# core09gnd.net
KiCad netlist of a schematic drawn in EAGLE
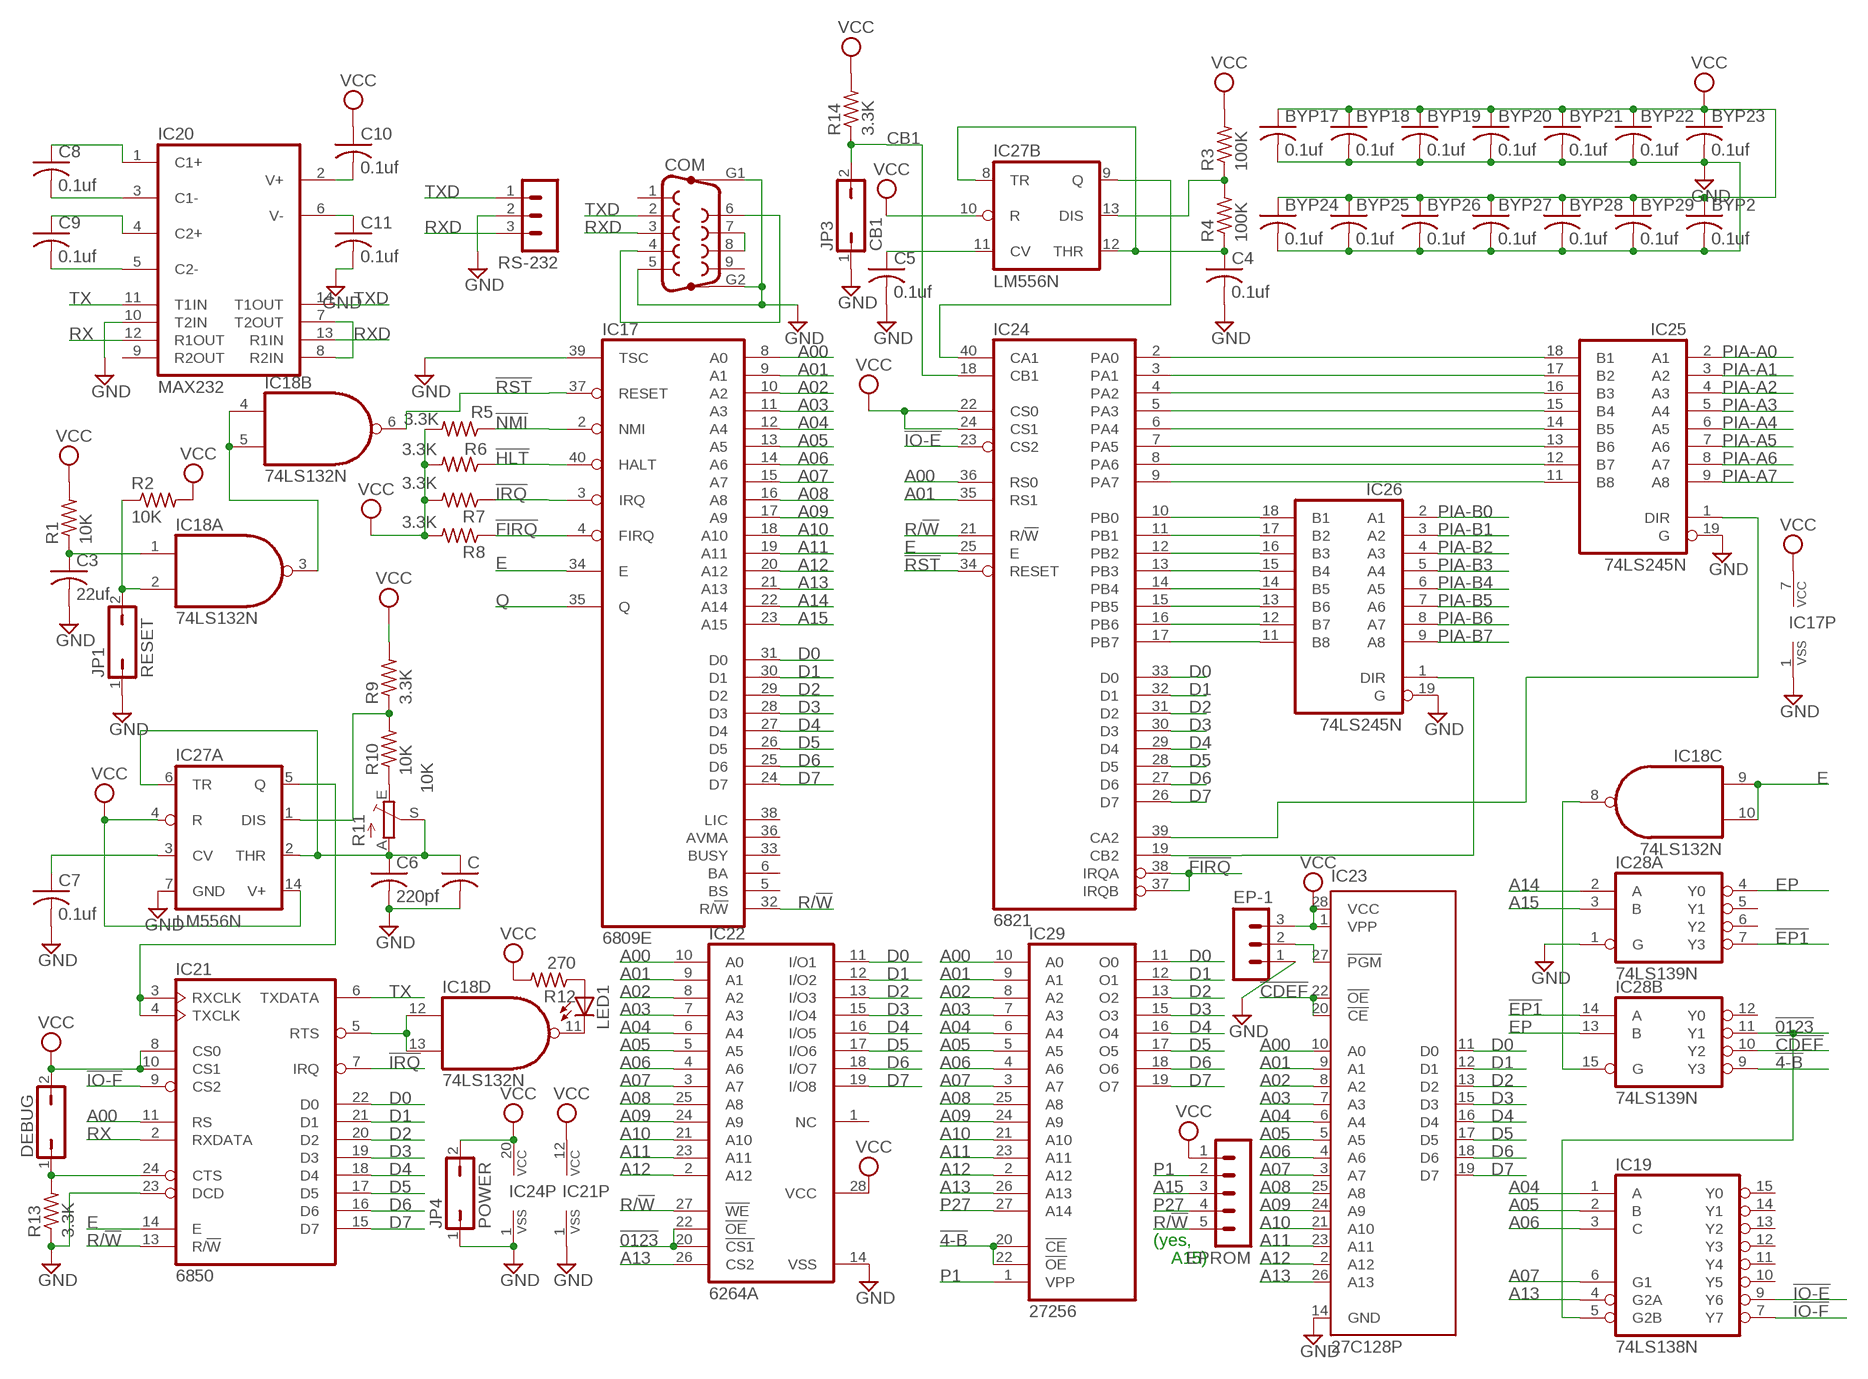
[diagram p0: schematic, sheet 1]
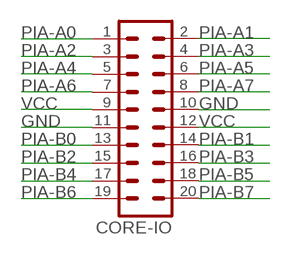
[diagram p1: schematic, sheet 2]
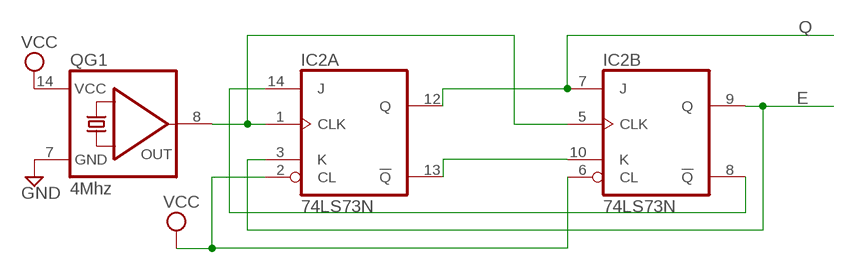
[diagram p2: schematic, sheet 3]

(export (version "E")
  (design (tool "Eeschema 10.0.6"))
  (components
    (comp (ref "CORE-IO")
      (value "MA10-2")
      (footprint "eagle-import:MA10-2")
      (libsource (lib "eagle-import") (part "MA10-2"))
    )
    (comp (ref "IC2")
      (value "74LS73N")
      (footprint "eagle-import:DIL14")
      (libsource (lib "eagle-import") (part "7473NLS"))
    )
    (comp (ref "QG1")
      (value "4Mhz")
      (footprint "eagle-import:DIL14S")
      (libsource (lib "eagle-import") (part "QG5860"))
    )
    (comp (ref "BYP2")
      (value "0.1uf")
      (footprint "eagle-import:C050-025X075")
      (libsource (lib "eagle-import") (part "C-US050-025X075"))
    )
    (comp (ref "BYP17")
      (value "0.1uf")
      (footprint "eagle-import:C050-025X075")
      (libsource (lib "eagle-import") (part "C-US050-025X075"))
    )
    (comp (ref "BYP18")
      (value "0.1uf")
      (footprint "eagle-import:C050-025X075")
      (libsource (lib "eagle-import") (part "C-US050-025X075"))
    )
    (comp (ref "BYP19")
      (value "0.1uf")
      (footprint "eagle-import:C050-025X075")
      (libsource (lib "eagle-import") (part "C-US050-025X075"))
    )
    (comp (ref "BYP20")
      (value "0.1uf")
      (footprint "eagle-import:C050-025X075")
      (libsource (lib "eagle-import") (part "C-US050-025X075"))
    )
    (comp (ref "BYP21")
      (value "0.1uf")
      (footprint "eagle-import:C050-025X075")
      (libsource (lib "eagle-import") (part "C-US050-025X075"))
    )
    (comp (ref "BYP22")
      (value "0.1uf")
      (footprint "eagle-import:C050-025X075")
      (libsource (lib "eagle-import") (part "C-US050-025X075"))
    )
    (comp (ref "BYP23")
      (value "0.1uf")
      (footprint "eagle-import:C050-025X075")
      (libsource (lib "eagle-import") (part "C-US050-025X075"))
    )
    (comp (ref "BYP24")
      (value "0.1uf")
      (footprint "eagle-import:C050-025X075")
      (libsource (lib "eagle-import") (part "C-US050-025X075"))
    )
    (comp (ref "BYP25")
      (value "0.1uf")
      (footprint "eagle-import:C050-025X075")
      (libsource (lib "eagle-import") (part "C-US050-025X075"))
    )
    (comp (ref "BYP26")
      (value "0.1uf")
      (footprint "eagle-import:C050-025X075")
      (libsource (lib "eagle-import") (part "C-US050-025X075"))
    )
    (comp (ref "BYP27")
      (value "0.1uf")
      (footprint "eagle-import:C050-025X075")
      (libsource (lib "eagle-import") (part "C-US050-025X075"))
    )
    (comp (ref "BYP28")
      (value "0.1uf")
      (footprint "eagle-import:C050-025X075")
      (libsource (lib "eagle-import") (part "C-US050-025X075"))
    )
    (comp (ref "BYP29")
      (value "0.1uf")
      (footprint "eagle-import:C050-025X075")
      (libsource (lib "eagle-import") (part "C-US050-025X075"))
    )
    (comp (ref "C")
      (value "C-US050-025X075")
      (footprint "eagle-import:C050-025X075")
      (libsource (lib "eagle-import") (part "C-US050-025X075"))
    )
    (comp (ref "C3")
      (value "22uf")
      (footprint "eagle-import:C102-054X133")
      (libsource (lib "eagle-import") (part "C-US102-054X133"))
    )
    (comp (ref "C4")
      (value "0.1uf")
      (footprint "eagle-import:C050-025X075")
      (libsource (lib "eagle-import") (part "C-US050-025X075"))
    )
    (comp (ref "C5")
      (value "0.1uf")
      (footprint "eagle-import:C050-025X075")
      (libsource (lib "eagle-import") (part "C-US050-025X075"))
    )
    (comp (ref "C6")
      (value "220pf")
      (footprint "eagle-import:C050-025X075")
      (libsource (lib "eagle-import") (part "C-US050-025X075"))
    )
    (comp (ref "C7")
      (value "0.1uf")
      (footprint "eagle-import:C050-025X075")
      (libsource (lib "eagle-import") (part "C-US050-025X075"))
    )
    (comp (ref "C8")
      (value "0.1uf")
      (footprint "eagle-import:C050-025X075")
      (libsource (lib "eagle-import") (part "C-US050-025X075"))
    )
    (comp (ref "C9")
      (value "0.1uf")
      (footprint "eagle-import:C050-025X075")
      (libsource (lib "eagle-import") (part "C-US050-025X075"))
    )
    (comp (ref "C10")
      (value "0.1uf")
      (footprint "eagle-import:C050-025X075")
      (libsource (lib "eagle-import") (part "C-US050-025X075"))
    )
    (comp (ref "C11")
      (value "0.1uf")
      (footprint "eagle-import:C050-025X075")
      (libsource (lib "eagle-import") (part "C-US050-025X075"))
    )
    (comp (ref "COM")
      (value "F09HP")
      (footprint "eagle-import:F09HP")
      (libsource (lib "eagle-import") (part "F09HP"))
    )
    (comp (ref "DEBUG")
      (value "JP1Q")
      (footprint "eagle-import:JP1")
      (libsource (lib "eagle-import") (part "JP1Q"))
    )
    (comp (ref "EP-1")
      (value "MA03-1")
      (footprint "eagle-import:MA03-1")
      (libsource (lib "eagle-import") (part "MA03-1"))
    )
    (comp (ref "EPROM")
      (value "MA05-1")
      (footprint "eagle-import:MA05-1")
      (libsource (lib "eagle-import") (part "MA05-1"))
    )
    (comp (ref "IC17")
      (value "6809E")
      (footprint "eagle-import:DIL40")
      (fields (field (name "MF") "NTE ELECTRONICS") (field (name "MPN") "NTE6809E"))
      (libsource (lib "eagle-import") (part "6809E"))
    )
    (comp (ref "IC18")
      (value "74LS132N")
      (footprint "eagle-import:DIL14")
      (libsource (lib "eagle-import") (part "7400NLS"))
    )
    (comp (ref "IC19")
      (value "74LS138N")
      (footprint "eagle-import:DIL16")
      (libsource (lib "eagle-import") (part "74138NLS"))
    )
    (comp (ref "IC20")
      (value "MAX232")
      (footprint "eagle-import:DIL16")
      (fields (field (name "MF") "MAXIM") (field (name "MPN") "MAX232ACPE+"))
      (libsource (lib "eagle-import") (part "MAX232"))
    )
    (comp (ref "IC21")
      (value "6850")
      (footprint "eagle-import:DIL24")
      (fields (field (name "MF") "NTE ELECTRONICS") (field (name "MPN") "NTE6850"))
      (libsource (lib "eagle-import") (part "6850"))
    )
    (comp (ref "IC22")
      (value "6264A")
      (footprint "eagle-import:DIL28-6")
      (libsource (lib "eagle-import") (part "6264A"))
    )
    (comp (ref "IC23")
      (value "27C128P")
      (footprint "eagle-import:DIL28-6")
      (libsource (lib "eagle-import") (part "27128PC"))
    )
    (comp (ref "IC24")
      (value "6821")
      (footprint "eagle-import:DIL40")
      (fields (field (name "MF") "NTE ELECTRONICS") (field (name "MPN") "NTE6821"))
      (libsource (lib "eagle-import") (part "6821"))
    )
    (comp (ref "IC25")
      (value "74LS245N")
      (footprint "eagle-import:DIL20")
      (libsource (lib "eagle-import") (part "74245NLS"))
    )
    (comp (ref "IC26")
      (value "74LS245N")
      (footprint "eagle-import:DIL20")
      (libsource (lib "eagle-import") (part "74245NLS"))
    )
    (comp (ref "IC27")
      (value "LM556N")
      (footprint "eagle-import:DIL14")
      (libsource (lib "eagle-import") (part "556NLM"))
    )
    (comp (ref "IC28")
      (value "74LS139N")
      (footprint "eagle-import:DIL16")
      (libsource (lib "eagle-import") (part "74139NLS"))
    )
    (comp (ref "IC29")
      (value "27256")
      (footprint "eagle-import:DIL28")
      (libsource (lib "eagle-import") (part "27256"))
    )
    (comp (ref "JP1")
      (value "RESET")
      (footprint "eagle-import:JP1")
      (libsource (lib "eagle-import") (part "JP1Q"))
    )
    (comp (ref "JP3")
      (value "CB1")
      (footprint "eagle-import:JP1")
      (libsource (lib "eagle-import") (part "JP1Q"))
    )
    (comp (ref "JP4")
      (value "POWER")
      (footprint "eagle-import:JP1")
      (libsource (lib "eagle-import") (part "JP1Q"))
    )
    (comp (ref "LED1")
      (value "LED3MM")
      (footprint "eagle-import:LED3MM")
      (libsource (lib "eagle-import") (part "LED3MM"))
    )
    (comp (ref "R1")
      (value "10K")
      (footprint "eagle-import:0207_7")
      (libsource (lib "eagle-import") (part "R-US_0207/7"))
    )
    (comp (ref "R2")
      (value "10K")
      (footprint "eagle-import:0207_7")
      (libsource (lib "eagle-import") (part "R-US_0207/7"))
    )
    (comp (ref "R3")
      (value "100K")
      (footprint "eagle-import:0207_7")
      (libsource (lib "eagle-import") (part "R-US_0207/7"))
    )
    (comp (ref "R4")
      (value "100K")
      (footprint "eagle-import:0207_7")
      (libsource (lib "eagle-import") (part "R-US_0207/7"))
    )
    (comp (ref "R5")
      (value "3.3K")
      (footprint "eagle-import:0207_7")
      (libsource (lib "eagle-import") (part "R-US_0207/7"))
    )
    (comp (ref "R6")
      (value "3.3K")
      (footprint "eagle-import:0207_7")
      (libsource (lib "eagle-import") (part "R-US_0207/7"))
    )
    (comp (ref "R7")
      (value "3.3K")
      (footprint "eagle-import:0207_7")
      (libsource (lib "eagle-import") (part "R-US_0207/7"))
    )
    (comp (ref "R8")
      (value "3.3K")
      (footprint "eagle-import:0207_7")
      (libsource (lib "eagle-import") (part "R-US_0207/7"))
    )
    (comp (ref "R9")
      (value "3.3K")
      (footprint "eagle-import:0207_7")
      (libsource (lib "eagle-import") (part "R-US_0207/7"))
    )
    (comp (ref "R10")
      (value "10K")
      (footprint "eagle-import:0207_7")
      (libsource (lib "eagle-import") (part "R-US_0207/7"))
    )
    (comp (ref "R11")
      (value "10K")
      (footprint "eagle-import:SP19L")
      (libsource (lib "eagle-import") (part "TRIM_EU-B90P"))
    )
    (comp (ref "R12")
      (value "270")
      (footprint "eagle-import:0207_7")
      (libsource (lib "eagle-import") (part "R-US_0207/7"))
    )
    (comp (ref "R13")
      (value "3.3K")
      (footprint "eagle-import:0207_7")
      (libsource (lib "eagle-import") (part "R-US_0207/7"))
    )
    (comp (ref "R14")
      (value "3.3K")
      (footprint "eagle-import:0207_7")
      (libsource (lib "eagle-import") (part "R-US_0207/7"))
    )
    (comp (ref "RS-232")
      (value "MA03-1")
      (footprint "eagle-import:MA03-1")
      (libsource (lib "eagle-import") (part "MA03-1"))
    )
  )
  (nets
    (net (code "1") (name "A00") (class "Default")
      (node (ref "IC17") (pin "8") (pinfunction "A0_8") (pintype "tri_state"))
      (node (ref "IC21") (pin "11") (pinfunction "RS_11") (pintype "input"))
      (node (ref "IC22") (pin "10") (pinfunction "A0_10") (pintype "input"))
      (node (ref "IC23") (pin "10") (pinfunction "A0_10") (pintype "input"))
      (node (ref "IC24") (pin "36") (pinfunction "RS0_36") (pintype "input"))
      (node (ref "IC29") (pin "10") (pinfunction "A0_10") (pintype "input"))
    )
    (net (code "2") (name "A01") (class "Default")
      (node (ref "IC17") (pin "9") (pinfunction "A1_9") (pintype "tri_state"))
      (node (ref "IC22") (pin "9") (pinfunction "A1_9") (pintype "input"))
      (node (ref "IC23") (pin "9") (pinfunction "A1_9") (pintype "input"))
      (node (ref "IC24") (pin "35") (pinfunction "RS1_35") (pintype "input"))
      (node (ref "IC29") (pin "9") (pinfunction "A1_9") (pintype "input"))
    )
    (net (code "3") (name "A02") (class "Default")
      (node (ref "IC17") (pin "10") (pinfunction "A2_10") (pintype "tri_state"))
      (node (ref "IC22") (pin "8") (pinfunction "A2_8") (pintype "input"))
      (node (ref "IC23") (pin "8") (pinfunction "A2_8") (pintype "input"))
      (node (ref "IC29") (pin "8") (pinfunction "A2_8") (pintype "input"))
    )
    (net (code "4") (name "A03") (class "Default")
      (node (ref "IC17") (pin "11") (pinfunction "A3_11") (pintype "tri_state"))
      (node (ref "IC22") (pin "7") (pinfunction "A3_7") (pintype "input"))
      (node (ref "IC23") (pin "7") (pinfunction "A3_7") (pintype "input"))
      (node (ref "IC29") (pin "7") (pinfunction "A3_7") (pintype "input"))
    )
    (net (code "5") (name "A04") (class "Default")
      (node (ref "IC17") (pin "12") (pinfunction "A4_12") (pintype "tri_state"))
      (node (ref "IC19") (pin "1") (pinfunction "A_1") (pintype "input"))
      (node (ref "IC22") (pin "6") (pinfunction "A4_6") (pintype "input"))
      (node (ref "IC23") (pin "6") (pinfunction "A4_6") (pintype "input"))
      (node (ref "IC29") (pin "6") (pinfunction "A4_6") (pintype "input"))
    )
    (net (code "6") (name "A05") (class "Default")
      (node (ref "IC17") (pin "13") (pinfunction "A5_13") (pintype "tri_state"))
      (node (ref "IC19") (pin "2") (pinfunction "B_2") (pintype "input"))
      (node (ref "IC22") (pin "5") (pinfunction "A5_5") (pintype "input"))
      (node (ref "IC23") (pin "5") (pinfunction "A5_5") (pintype "input"))
      (node (ref "IC29") (pin "5") (pinfunction "A5_5") (pintype "input"))
    )
    (net (code "7") (name "A06") (class "Default")
      (node (ref "IC17") (pin "14") (pinfunction "A6_14") (pintype "tri_state"))
      (node (ref "IC19") (pin "3") (pinfunction "C_3") (pintype "input"))
      (node (ref "IC22") (pin "4") (pinfunction "A6_4") (pintype "input"))
      (node (ref "IC23") (pin "4") (pinfunction "A6_4") (pintype "input"))
      (node (ref "IC29") (pin "4") (pinfunction "A6_4") (pintype "input"))
    )
    (net (code "8") (name "A07") (class "Default")
      (node (ref "IC17") (pin "15") (pinfunction "A7_15") (pintype "tri_state"))
      (node (ref "IC19") (pin "6") (pinfunction "G1_6") (pintype "input"))
      (node (ref "IC22") (pin "3") (pinfunction "A7_3") (pintype "input"))
      (node (ref "IC23") (pin "3") (pinfunction "A7_3") (pintype "input"))
      (node (ref "IC29") (pin "3") (pinfunction "A7_3") (pintype "input"))
    )
    (net (code "9") (name "A08") (class "Default")
      (node (ref "IC17") (pin "16") (pinfunction "A8_16") (pintype "tri_state"))
      (node (ref "IC22") (pin "25") (pinfunction "A8_25") (pintype "input"))
      (node (ref "IC23") (pin "25") (pinfunction "A8_25") (pintype "input"))
      (node (ref "IC29") (pin "25") (pinfunction "A8_25") (pintype "input"))
    )
    (net (code "10") (name "A09") (class "Default")
      (node (ref "IC17") (pin "17") (pinfunction "A9_17") (pintype "tri_state"))
      (node (ref "IC22") (pin "24") (pinfunction "A9_24") (pintype "input"))
      (node (ref "IC23") (pin "24") (pinfunction "A9_24") (pintype "input"))
      (node (ref "IC29") (pin "24") (pinfunction "A9_24") (pintype "input"))
    )
    (net (code "11") (name "A10") (class "Default")
      (node (ref "IC17") (pin "18") (pinfunction "A10_18") (pintype "tri_state"))
      (node (ref "IC22") (pin "21") (pinfunction "A10_21") (pintype "input"))
      (node (ref "IC23") (pin "21") (pinfunction "A10_21") (pintype "input"))
      (node (ref "IC29") (pin "21") (pinfunction "A10_21") (pintype "input"))
    )
    (net (code "12") (name "A11") (class "Default")
      (node (ref "IC17") (pin "19") (pinfunction "A11_19") (pintype "tri_state"))
      (node (ref "IC22") (pin "23") (pinfunction "A11_23") (pintype "input"))
      (node (ref "IC23") (pin "23") (pinfunction "A11_23") (pintype "input"))
      (node (ref "IC29") (pin "23") (pinfunction "A11_23") (pintype "input"))
    )
    (net (code "13") (name "A12") (class "Default")
      (node (ref "IC17") (pin "20") (pinfunction "A12_20") (pintype "tri_state"))
      (node (ref "IC22") (pin "2") (pinfunction "A12_2") (pintype "input"))
      (node (ref "IC23") (pin "2") (pinfunction "A12_2") (pintype "input"))
      (node (ref "IC29") (pin "2") (pinfunction "A12_2") (pintype "input"))
    )
    (net (code "14") (name "A13") (class "Default")
      (node (ref "IC17") (pin "21") (pinfunction "A13_21") (pintype "tri_state"))
      (node (ref "IC19") (pin "4") (pinfunction "G2A_4") (pintype "input"))
      (node (ref "IC22") (pin "26") (pinfunction "CS2_26") (pintype "input"))
      (node (ref "IC23") (pin "26") (pinfunction "A13_26") (pintype "input"))
      (node (ref "IC29") (pin "26") (pinfunction "A13_26") (pintype "input"))
    )
    (net (code "15") (name "A14") (class "Default")
      (node (ref "IC17") (pin "22") (pinfunction "A14_22") (pintype "tri_state"))
      (node (ref "IC28") (pin "2") (pinfunction "A_2") (pintype "input"))
    )
    (net (code "16") (name "A15") (class "Default")
      (node (ref "EPROM") (pin "3") (pinfunction "3_3") (pintype "passive"))
      (node (ref "IC17") (pin "23") (pinfunction "A15_23") (pintype "tri_state"))
      (node (ref "IC28") (pin "3") (pinfunction "B_3") (pintype "input"))
    )
    (net (code "17") (name "CB1") (class "Default")
      (node (ref "IC24") (pin "18") (pinfunction "CB1_18") (pintype "input"))
      (node (ref "JP3") (pin "2") (pinfunction "2_2") (pintype "passive"))
      (node (ref "R14") (pin "1") (pinfunction "1_1") (pintype "passive"))
    )
    (net (code "18") (name "D0") (class "Default")
      (node (ref "IC17") (pin "31") (pinfunction "D0_31") (pintype "bidirectional"))
      (node (ref "IC21") (pin "22") (pinfunction "D0_22") (pintype "bidirectional"))
      (node (ref "IC22") (pin "11") (pinfunction "I/O1_11") (pintype "bidirectional"))
      (node (ref "IC23") (pin "11") (pinfunction "D0_11") (pintype "tri_state"))
      (node (ref "IC24") (pin "33") (pinfunction "D0_33") (pintype "bidirectional"))
      (node (ref "IC29") (pin "11") (pinfunction "O0_11") (pintype "tri_state"))
    )
    (net (code "19") (name "D1") (class "Default")
      (node (ref "IC17") (pin "30") (pinfunction "D1_30") (pintype "bidirectional"))
      (node (ref "IC21") (pin "21") (pinfunction "D1_21") (pintype "bidirectional"))
      (node (ref "IC22") (pin "12") (pinfunction "I/O2_12") (pintype "bidirectional"))
      (node (ref "IC23") (pin "12") (pinfunction "D1_12") (pintype "tri_state"))
      (node (ref "IC24") (pin "32") (pinfunction "D1_32") (pintype "bidirectional"))
      (node (ref "IC29") (pin "12") (pinfunction "O1_12") (pintype "tri_state"))
    )
    (net (code "20") (name "D2") (class "Default")
      (node (ref "IC17") (pin "29") (pinfunction "D2_29") (pintype "bidirectional"))
      (node (ref "IC21") (pin "20") (pinfunction "D2_20") (pintype "bidirectional"))
      (node (ref "IC22") (pin "13") (pinfunction "I/O3_13") (pintype "bidirectional"))
      (node (ref "IC23") (pin "13") (pinfunction "D2_13") (pintype "tri_state"))
      (node (ref "IC24") (pin "31") (pinfunction "D2_31") (pintype "bidirectional"))
      (node (ref "IC29") (pin "13") (pinfunction "O2_13") (pintype "tri_state"))
    )
    (net (code "21") (name "D3") (class "Default")
      (node (ref "IC17") (pin "28") (pinfunction "D3_28") (pintype "bidirectional"))
      (node (ref "IC21") (pin "19") (pinfunction "D3_19") (pintype "bidirectional"))
      (node (ref "IC22") (pin "15") (pinfunction "I/O4_15") (pintype "bidirectional"))
      (node (ref "IC23") (pin "15") (pinfunction "D3_15") (pintype "tri_state"))
      (node (ref "IC24") (pin "30") (pinfunction "D3_30") (pintype "bidirectional"))
      (node (ref "IC29") (pin "15") (pinfunction "O3_15") (pintype "tri_state"))
    )
    (net (code "22") (name "D4") (class "Default")
      (node (ref "IC17") (pin "27") (pinfunction "D4_27") (pintype "bidirectional"))
      (node (ref "IC21") (pin "18") (pinfunction "D4_18") (pintype "bidirectional"))
      (node (ref "IC22") (pin "16") (pinfunction "I/O5_16") (pintype "bidirectional"))
      (node (ref "IC23") (pin "16") (pinfunction "D4_16") (pintype "tri_state"))
      (node (ref "IC24") (pin "29") (pinfunction "D4_29") (pintype "bidirectional"))
      (node (ref "IC29") (pin "16") (pinfunction "O4_16") (pintype "tri_state"))
    )
    (net (code "23") (name "D5") (class "Default")
      (node (ref "IC17") (pin "26") (pinfunction "D5_26") (pintype "bidirectional"))
      (node (ref "IC21") (pin "17") (pinfunction "D5_17") (pintype "bidirectional"))
      (node (ref "IC22") (pin "17") (pinfunction "I/O6_17") (pintype "bidirectional"))
      (node (ref "IC23") (pin "17") (pinfunction "D5_17") (pintype "tri_state"))
      (node (ref "IC24") (pin "28") (pinfunction "D5_28") (pintype "bidirectional"))
      (node (ref "IC29") (pin "17") (pinfunction "O5_17") (pintype "tri_state"))
    )
    (net (code "24") (name "D6") (class "Default")
      (node (ref "IC17") (pin "25") (pinfunction "D6_25") (pintype "bidirectional"))
      (node (ref "IC21") (pin "16") (pinfunction "D6_16") (pintype "bidirectional"))
      (node (ref "IC22") (pin "18") (pinfunction "I/O7_18") (pintype "bidirectional"))
      (node (ref "IC23") (pin "18") (pinfunction "D6_18") (pintype "tri_state"))
      (node (ref "IC24") (pin "27") (pinfunction "D6_27") (pintype "bidirectional"))
      (node (ref "IC29") (pin "18") (pinfunction "O6_18") (pintype "tri_state"))
    )
    (net (code "25") (name "D7") (class "Default")
      (node (ref "IC17") (pin "24") (pinfunction "D7_24") (pintype "bidirectional"))
      (node (ref "IC21") (pin "15") (pinfunction "D7_15") (pintype "bidirectional"))
      (node (ref "IC22") (pin "19") (pinfunction "I/O8_19") (pintype "bidirectional"))
      (node (ref "IC23") (pin "19") (pinfunction "D7_19") (pintype "tri_state"))
      (node (ref "IC24") (pin "26") (pinfunction "D7_26") (pintype "bidirectional"))
      (node (ref "IC29") (pin "19") (pinfunction "O7_19") (pintype "tri_state"))
    )
    (net (code "26") (name "E") (class "Default")
      (node (ref "IC17") (pin "34") (pinfunction "E_34") (pintype "input"))
      (node (ref "IC18") (pin "10") (pinfunction "I1_10") (pintype "input"))
      (node (ref "IC18") (pin "9") (pinfunction "I0_9") (pintype "input"))
      (node (ref "IC2") (pin "3") (pinfunction "K_3") (pintype "input"))
      (node (ref "IC2") (pin "9") (pinfunction "Q_9") (pintype "output"))
      (node (ref "IC21") (pin "14") (pinfunction "E_14") (pintype "input"))
      (node (ref "IC24") (pin "25") (pinfunction "E_25") (pintype "input"))
    )
    (net (code "27") (name "EP") (class "Default")
      (node (ref "IC28") (pin "13") (pinfunction "B_13") (pintype "input"))
      (node (ref "IC28") (pin "4") (pinfunction "Y0_4") (pintype "output"))
    )
    (net (code "28") (name "GND") (class "Default")
      (node (ref "BYP17") (pin "2") (pinfunction "2_2") (pintype "passive"))
      (node (ref "BYP18") (pin "2") (pinfunction "2_2") (pintype "passive"))
      (node (ref "BYP19") (pin "2") (pinfunction "2_2") (pintype "passive"))
      (node (ref "BYP2") (pin "2") (pinfunction "2_2") (pintype "passive"))
      (node (ref "BYP20") (pin "2") (pinfunction "2_2") (pintype "passive"))
      (node (ref "BYP21") (pin "2") (pinfunction "2_2") (pintype "passive"))
      (node (ref "BYP22") (pin "2") (pinfunction "2_2") (pintype "passive"))
      (node (ref "BYP23") (pin "2") (pinfunction "2_2") (pintype "passive"))
      (node (ref "BYP24") (pin "2") (pinfunction "2_2") (pintype "passive"))
      (node (ref "BYP25") (pin "2") (pinfunction "2_2") (pintype "passive"))
      (node (ref "BYP26") (pin "2") (pinfunction "2_2") (pintype "passive"))
      (node (ref "BYP27") (pin "2") (pinfunction "2_2") (pintype "passive"))
      (node (ref "BYP28") (pin "2") (pinfunction "2_2") (pintype "passive"))
      (node (ref "BYP29") (pin "2") (pinfunction "2_2") (pintype "passive"))
      (node (ref "C") (pin "2") (pinfunction "2_2") (pintype "passive"))
      (node (ref "C11") (pin "2") (pinfunction "2_2") (pintype "passive"))
      (node (ref "C3") (pin "2") (pinfunction "2_2") (pintype "passive"))
      (node (ref "C4") (pin "2") (pinfunction "2_2") (pintype "passive"))
      (node (ref "C5") (pin "2") (pinfunction "2_2") (pintype "passive"))
      (node (ref "C6") (pin "2") (pinfunction "2_2") (pintype "passive"))
      (node (ref "C7") (pin "2") (pinfunction "2_2") (pintype "passive"))
      (node (ref "COM") (pin "5") (pinfunction "5_5") (pintype "passive"))
      (node (ref "COM") (pin "G1") (pinfunction "G1_G1") (pintype "passive"))
      (node (ref "COM") (pin "G2") (pinfunction "G2_G2") (pintype "passive"))
      (node (ref "CORE-IO") (pin "10") (pinfunction "10_10") (pintype "passive"))
      (node (ref "CORE-IO") (pin "11") (pinfunction "11_11") (pintype "passive"))
      (node (ref "EP-1") (pin "1") (pinfunction "1_1") (pintype "passive"))
      (node (ref "IC17") (pin "1") (pinfunction "VSS_1") (pintype "power_in"))
      (node (ref "IC17") (pin "39") (pinfunction "TSC_39") (pintype "input"))
      (node (ref "IC20") (pin "10") (pinfunction "T2IN_10") (pintype "input"))
      (node (ref "IC21") (pin "1") (pinfunction "VSS_1") (pintype "power_in"))
      (node (ref "IC21") (pin "23") (pinfunction "DCD_23") (pintype "input"))
      (node (ref "IC22") (pin "14") (pinfunction "VSS_14") (pintype "power_in"))
      (node (ref "IC23") (pin "14") (pinfunction "GND_14") (pintype "power_in"))
      (node (ref "IC24") (pin "1") (pinfunction "VSS_1") (pintype "power_in"))
      (node (ref "IC25") (pin "19") (pinfunction "G_19") (pintype "input"))
      (node (ref "IC26") (pin "19") (pinfunction "G_19") (pintype "input"))
      (node (ref "IC27") (pin "7") (pinfunction "GND_7") (pintype "power_in"))
      (node (ref "IC28") (pin "1") (pinfunction "G_1") (pintype "input"))
      (node (ref "JP1") (pin "1") (pinfunction "1_1") (pintype "passive"))
      (node (ref "JP3") (pin "1") (pinfunction "1_1") (pintype "passive"))
      (node (ref "JP4") (pin "1") (pinfunction "1_1") (pintype "passive"))
      (node (ref "QG1") (pin "7") (pinfunction "GND_7") (pintype "power_in"))
      (node (ref "R13") (pin "1") (pinfunction "1_1") (pintype "passive"))
      (node (ref "RS-232") (pin "2") (pinfunction "2_2") (pintype "passive"))
    )
    (net (code "29") (name "Net-(COM-Pad4)") (class "Default")
      (node (ref "COM") (pin "4") (pinfunction "4_4") (pintype "passive"))
      (node (ref "COM") (pin "6") (pinfunction "6_6") (pintype "passive"))
    )
    (net (code "30") (name "Net-(COM-Pad7)") (class "Default")
      (node (ref "COM") (pin "7") (pinfunction "7_7") (pintype "passive"))
      (node (ref "COM") (pin "8") (pinfunction "8_8") (pintype "passive"))
    )
    (net (code "31") (name "Net-(IC2A-CLK)") (class "Default")
      (node (ref "IC2") (pin "1") (pinfunction "CLK_1") (pintype "input"))
      (node (ref "IC2") (pin "5") (pinfunction "CLK_5") (pintype "input"))
      (node (ref "QG1") (pin "8") (pinfunction "OUT_8") (pintype "output"))
    )
    (net (code "32") (name "Net-(IC2A-J)") (class "Default")
      (node (ref "IC2") (pin "14") (pinfunction "J_14") (pintype "input"))
      (node (ref "IC2") (pin "8") (pinfunction "~{Q}_8") (pintype "output"))
    )
    (net (code "33") (name "Net-(IC2A-~{Q})") (class "Default")
      (node (ref "IC2") (pin "10") (pinfunction "K_10") (pintype "input"))
      (node (ref "IC2") (pin "13") (pinfunction "~{Q}_13") (pintype "output"))
    )
    (net (code "34") (name "Net-(IC18A-I0)") (class "Default")
      (node (ref "C3") (pin "1") (pinfunction "1_1") (pintype "passive"))
      (node (ref "IC18") (pin "1") (pinfunction "I0_1") (pintype "input"))
      (node (ref "R1") (pin "1") (pinfunction "1_1") (pintype "passive"))
    )
    (net (code "35") (name "Net-(IC18A-I1)") (class "Default")
      (node (ref "IC18") (pin "2") (pinfunction "I1_2") (pintype "input"))
      (node (ref "JP1") (pin "2") (pinfunction "2_2") (pintype "passive"))
      (node (ref "R2") (pin "1") (pinfunction "1_1") (pintype "passive"))
    )
    (net (code "36") (name "Net-(IC18A-O)") (class "Default")
      (node (ref "IC18") (pin "3") (pinfunction "O_3") (pintype "output"))
      (node (ref "IC18") (pin "4") (pinfunction "I0_4") (pintype "input"))
      (node (ref "IC18") (pin "5") (pinfunction "I1_5") (pintype "input"))
    )
    (net (code "37") (name "Net-(IC18C-O)") (class "Default")
      (node (ref "IC18") (pin "8") (pinfunction "O_8") (pintype "output"))
      (node (ref "IC28") (pin "15") (pinfunction "G_15") (pintype "input"))
    )
    (net (code "38") (name "Net-(IC18D-I0)") (class "Default")
      (node (ref "IC18") (pin "12") (pinfunction "I0_12") (pintype "input"))
      (node (ref "IC18") (pin "13") (pinfunction "I1_13") (pintype "input"))
      (node (ref "IC21") (pin "5") (pinfunction "RTS_5") (pintype "output"))
    )
    (net (code "39") (name "Net-(IC18D-O)") (class "Default")
      (node (ref "IC18") (pin "11") (pinfunction "O_11") (pintype "output"))
      (node (ref "LED1") (pin "K") (pinfunction "C_K") (pintype "passive"))
    )
    (net (code "40") (name "Net-(IC20A-C1+)") (class "Default")
      (node (ref "C8") (pin "1") (pinfunction "1_1") (pintype "passive"))
      (node (ref "IC20") (pin "1") (pinfunction "C1+_1") (pintype "bidirectional"))
    )
    (net (code "41") (name "Net-(IC20A-C1-)") (class "Default")
      (node (ref "C8") (pin "2") (pinfunction "2_2") (pintype "passive"))
      (node (ref "IC20") (pin "3") (pinfunction "C1-_3") (pintype "bidirectional"))
    )
    (net (code "42") (name "Net-(IC20A-C2+)") (class "Default")
      (node (ref "C9") (pin "1") (pinfunction "1_1") (pintype "passive"))
      (node (ref "IC20") (pin "4") (pinfunction "C2+_4") (pintype "bidirectional"))
    )
    (net (code "43") (name "Net-(IC20A-C2-)") (class "Default")
      (node (ref "C9") (pin "2") (pinfunction "2_2") (pintype "passive"))
      (node (ref "IC20") (pin "5") (pinfunction "C2-_5") (pintype "bidirectional"))
    )
    (net (code "44") (name "Net-(IC20A-R2IN)") (class "Default")
      (node (ref "IC20") (pin "7") (pinfunction "T2OUT_7") (pintype "output"))
      (node (ref "IC20") (pin "8") (pinfunction "R2IN_8") (pintype "input"))
    )
    (net (code "45") (name "Net-(IC20A-V+)") (class "Default")
      (node (ref "C10") (pin "2") (pinfunction "2_2") (pintype "passive"))
      (node (ref "IC20") (pin "2") (pinfunction "V+_2") (pintype "bidirectional"))
    )
    (net (code "46") (name "Net-(IC20A-V-)") (class "Default")
      (node (ref "C11") (pin "1") (pinfunction "1_1") (pintype "passive"))
      (node (ref "IC20") (pin "6") (pinfunction "V-_6") (pintype "bidirectional"))
    )
    (net (code "47") (name "Net-(IC21A-CTS)") (class "Default")
      (node (ref "DEBUG") (pin "1") (pinfunction "1_1") (pintype "passive"))
      (node (ref "IC21") (pin "24") (pinfunction "CTS_24") (pintype "input"))
      (node (ref "R13") (pin "2") (pinfunction "2_2") (pintype "passive"))
    )
    (net (code "48") (name "Net-(IC21A-RXCLK)") (class "Default")
      (node (ref "IC21") (pin "3") (pinfunction "RXCLK_3") (pintype "input"))
      (node (ref "IC21") (pin "4") (pinfunction "TXCLK_4") (pintype "input"))
      (node (ref "IC27") (pin "5") (pinfunction "Q_5") (pintype "output"))
    )
    (net (code "49") (name "Net-(IC23-~{PGM})") (class "Default")
      (node (ref "EP-1") (pin "2") (pinfunction "2_2") (pintype "passive"))
      (node (ref "IC23") (pin "27") (pinfunction "~{PGM}_27") (pintype "passive"))
    )
    (net (code "50") (name "Net-(IC24A-CA1)") (class "Default")
      (node (ref "IC24") (pin "40") (pinfunction "CA1_40") (pintype "input"))
      (node (ref "IC27") (pin "9") (pinfunction "Q_9") (pintype "output"))
    )
    (net (code "51") (name "Net-(IC24A-CA2)") (class "Default")
      (node (ref "IC24") (pin "39") (pinfunction "CA2_39") (pintype "bidirectional"))
      (node (ref "IC25") (pin "1") (pinfunction "DIR_1") (pintype "input"))
    )
    (net (code "52") (name "Net-(IC24A-CB2)") (class "Default")
      (node (ref "IC24") (pin "19") (pinfunction "CB2_19") (pintype "bidirectional"))
      (node (ref "IC26") (pin "1") (pinfunction "DIR_1") (pintype "input"))
    )
    (net (code "53") (name "Net-(IC24A-PA0)") (class "Default")
      (node (ref "IC24") (pin "2") (pinfunction "PA0_2") (pintype "bidirectional"))
      (node (ref "IC25") (pin "18") (pinfunction "B1_18") (pintype "bidirectional"))
    )
    (net (code "54") (name "Net-(IC24A-PA1)") (class "Default")
      (node (ref "IC24") (pin "3") (pinfunction "PA1_3") (pintype "bidirectional"))
      (node (ref "IC25") (pin "17") (pinfunction "B2_17") (pintype "bidirectional"))
    )
    (net (code "55") (name "Net-(IC24A-PA2)") (class "Default")
      (node (ref "IC24") (pin "4") (pinfunction "PA2_4") (pintype "bidirectional"))
      (node (ref "IC25") (pin "16") (pinfunction "B3_16") (pintype "bidirectional"))
    )
    (net (code "56") (name "Net-(IC24A-PA3)") (class "Default")
      (node (ref "IC24") (pin "5") (pinfunction "PA3_5") (pintype "bidirectional"))
      (node (ref "IC25") (pin "15") (pinfunction "B4_15") (pintype "bidirectional"))
    )
    (net (code "57") (name "Net-(IC24A-PA4)") (class "Default")
      (node (ref "IC24") (pin "6") (pinfunction "PA4_6") (pintype "bidirectional"))
      (node (ref "IC25") (pin "14") (pinfunction "B5_14") (pintype "bidirectional"))
    )
    (net (code "58") (name "Net-(IC24A-PA5)") (class "Default")
      (node (ref "IC24") (pin "7") (pinfunction "PA5_7") (pintype "bidirectional"))
      (node (ref "IC25") (pin "13") (pinfunction "B6_13") (pintype "bidirectional"))
    )
    (net (code "59") (name "Net-(IC24A-PA6)") (class "Default")
      (node (ref "IC24") (pin "8") (pinfunction "PA6_8") (pintype "bidirectional"))
      (node (ref "IC25") (pin "12") (pinfunction "B7_12") (pintype "bidirectional"))
    )
    (net (code "60") (name "Net-(IC24A-PA7)") (class "Default")
      (node (ref "IC24") (pin "9") (pinfunction "PA7_9") (pintype "bidirectional"))
      (node (ref "IC25") (pin "11") (pinfunction "B8_11") (pintype "bidirectional"))
    )
    (net (code "61") (name "Net-(IC24A-PB0)") (class "Default")
      (node (ref "IC24") (pin "10") (pinfunction "PB0_10") (pintype "bidirectional"))
      (node (ref "IC26") (pin "18") (pinfunction "B1_18") (pintype "bidirectional"))
    )
    (net (code "62") (name "Net-(IC24A-PB1)") (class "Default")
      (node (ref "IC24") (pin "11") (pinfunction "PB1_11") (pintype "bidirectional"))
      (node (ref "IC26") (pin "17") (pinfunction "B2_17") (pintype "bidirectional"))
    )
    (net (code "63") (name "Net-(IC24A-PB2)") (class "Default")
      (node (ref "IC24") (pin "12") (pinfunction "PB2_12") (pintype "bidirectional"))
      (node (ref "IC26") (pin "16") (pinfunction "B3_16") (pintype "bidirectional"))
    )
    (net (code "64") (name "Net-(IC24A-PB3)") (class "Default")
      (node (ref "IC24") (pin "13") (pinfunction "PB3_13") (pintype "bidirectional"))
      (node (ref "IC26") (pin "15") (pinfunction "B4_15") (pintype "bidirectional"))
    )
    (net (code "65") (name "Net-(IC24A-PB4)") (class "Default")
      (node (ref "IC24") (pin "14") (pinfunction "PB4_14") (pintype "bidirectional"))
      (node (ref "IC26") (pin "14") (pinfunction "B5_14") (pintype "bidirectional"))
    )
    (net (code "66") (name "Net-(IC24A-PB5)") (class "Default")
      (node (ref "IC24") (pin "15") (pinfunction "PB5_15") (pintype "bidirectional"))
      (node (ref "IC26") (pin "13") (pinfunction "B6_13") (pintype "bidirectional"))
    )
    (net (code "67") (name "Net-(IC24A-PB6)") (class "Default")
      (node (ref "IC24") (pin "16") (pinfunction "PB6_16") (pintype "bidirectional"))
      (node (ref "IC26") (pin "12") (pinfunction "B7_12") (pintype "bidirectional"))
    )
    (net (code "68") (name "Net-(IC24A-PB7)") (class "Default")
      (node (ref "IC24") (pin "17") (pinfunction "PB7_17") (pintype "bidirectional"))
      (node (ref "IC26") (pin "11") (pinfunction "B8_11") (pintype "bidirectional"))
    )
    (net (code "69") (name "Net-(IC27A-CV)") (class "Default")
      (node (ref "C7") (pin "1") (pinfunction "1_1") (pintype "passive"))
      (node (ref "IC27") (pin "3") (pinfunction "CV_3") (pintype "input"))
    )
    (net (code "70") (name "Net-(IC27A-DIS)") (class "Default")
      (node (ref "IC27") (pin "1") (pinfunction "DIS_1") (pintype "input"))
      (node (ref "R10") (pin "2") (pinfunction "2_2") (pintype "passive"))
      (node (ref "R9") (pin "1") (pinfunction "1_1") (pintype "passive"))
    )
    (net (code "71") (name "Net-(IC27A-THR)") (class "Default")
      (node (ref "C") (pin "1") (pinfunction "1_1") (pintype "passive"))
      (node (ref "C6") (pin "1") (pinfunction "1_1") (pintype "passive"))
      (node (ref "IC27") (pin "2") (pinfunction "THR_2") (pintype "input"))
      (node (ref "IC27") (pin "6") (pinfunction "TR_6") (pintype "input"))
      (node (ref "R11") (pin "A") (pinfunction "A_A") (pintype "passive"))
      (node (ref "R11") (pin "S") (pinfunction "S_S") (pintype "passive"))
    )
    (net (code "72") (name "Net-(IC27B-CV)") (class "Default")
      (node (ref "C5") (pin "1") (pinfunction "1_1") (pintype "passive"))
      (node (ref "IC27") (pin "11") (pinfunction "CV_11") (pintype "input"))
    )
    (net (code "73") (name "Net-(IC27B-DIS)") (class "Default")
      (node (ref "IC27") (pin "13") (pinfunction "DIS_13") (pintype "input"))
      (node (ref "R3") (pin "1") (pinfunction "1_1") (pintype "passive"))
      (node (ref "R4") (pin "2") (pinfunction "2_2") (pintype "passive"))
    )
    (net (code "74") (name "Net-(IC27B-THR)") (class "Default")
      (node (ref "C4") (pin "1") (pinfunction "1_1") (pintype "passive"))
      (node (ref "IC27") (pin "12") (pinfunction "THR_12") (pintype "input"))
      (node (ref "IC27") (pin "8") (pinfunction "TR_8") (pintype "input"))
      (node (ref "R4") (pin "1") (pinfunction "1_1") (pintype "passive"))
    )
    (net (code "75") (name "Net-(LED1-PadA)") (class "Default")
      (node (ref "LED1") (pin "A") (pinfunction "A_A") (pintype "passive"))
      (node (ref "R12") (pin "1") (pinfunction "1_1") (pintype "passive"))
    )
    (net (code "76") (name "Net-(R10-Pad1)") (class "Default")
      (node (ref "R10") (pin "1") (pinfunction "1_1") (pintype "passive"))
      (node (ref "R11") (pin "E") (pinfunction "E_E") (pintype "passive"))
    )
    (net (code "77") (name "P1") (class "Default")
      (node (ref "EPROM") (pin "2") (pinfunction "2_2") (pintype "passive"))
      (node (ref "IC29") (pin "1") (pinfunction "VPP_1") (pintype "input"))
    )
    (net (code "78") (name "P27") (class "Default")
      (node (ref "EPROM") (pin "4") (pinfunction "4_4") (pintype "passive"))
      (node (ref "IC29") (pin "27") (pinfunction "A14_27") (pintype "input"))
    )
    (net (code "79") (name "PIA-A0") (class "Default")
      (node (ref "CORE-IO") (pin "1") (pinfunction "1_1") (pintype "passive"))
      (node (ref "IC25") (pin "2") (pinfunction "A1_2") (pintype "bidirectional"))
    )
    (net (code "80") (name "PIA-A1") (class "Default")
      (node (ref "CORE-IO") (pin "2") (pinfunction "2_2") (pintype "passive"))
      (node (ref "IC25") (pin "3") (pinfunction "A2_3") (pintype "bidirectional"))
    )
    (net (code "81") (name "PIA-A2") (class "Default")
      (node (ref "CORE-IO") (pin "3") (pinfunction "3_3") (pintype "passive"))
      (node (ref "IC25") (pin "4") (pinfunction "A3_4") (pintype "bidirectional"))
    )
    (net (code "82") (name "PIA-A3") (class "Default")
      (node (ref "CORE-IO") (pin "4") (pinfunction "4_4") (pintype "passive"))
      (node (ref "IC25") (pin "5") (pinfunction "A4_5") (pintype "bidirectional"))
    )
    (net (code "83") (name "PIA-A4") (class "Default")
      (node (ref "CORE-IO") (pin "5") (pinfunction "5_5") (pintype "passive"))
      (node (ref "IC25") (pin "6") (pinfunction "A5_6") (pintype "bidirectional"))
    )
    (net (code "84") (name "PIA-A5") (class "Default")
      (node (ref "CORE-IO") (pin "6") (pinfunction "6_6") (pintype "passive"))
      (node (ref "IC25") (pin "7") (pinfunction "A6_7") (pintype "bidirectional"))
    )
    (net (code "85") (name "PIA-A6") (class "Default")
      (node (ref "CORE-IO") (pin "7") (pinfunction "7_7") (pintype "passive"))
      (node (ref "IC25") (pin "8") (pinfunction "A7_8") (pintype "bidirectional"))
    )
    (net (code "86") (name "PIA-A7") (class "Default")
      (node (ref "CORE-IO") (pin "8") (pinfunction "8_8") (pintype "passive"))
      (node (ref "IC25") (pin "9") (pinfunction "A8_9") (pintype "bidirectional"))
    )
    (net (code "87") (name "PIA-B0") (class "Default")
      (node (ref "CORE-IO") (pin "13") (pinfunction "13_13") (pintype "passive"))
      (node (ref "IC26") (pin "2") (pinfunction "A1_2") (pintype "bidirectional"))
    )
    (net (code "88") (name "PIA-B1") (class "Default")
      (node (ref "CORE-IO") (pin "14") (pinfunction "14_14") (pintype "passive"))
      (node (ref "IC26") (pin "3") (pinfunction "A2_3") (pintype "bidirectional"))
    )
    (net (code "89") (name "PIA-B2") (class "Default")
      (node (ref "CORE-IO") (pin "15") (pinfunction "15_15") (pintype "passive"))
      (node (ref "IC26") (pin "4") (pinfunction "A3_4") (pintype "bidirectional"))
    )
    (net (code "90") (name "PIA-B3") (class "Default")
      (node (ref "CORE-IO") (pin "16") (pinfunction "16_16") (pintype "passive"))
      (node (ref "IC26") (pin "5") (pinfunction "A4_5") (pintype "bidirectional"))
    )
    (net (code "91") (name "PIA-B4") (class "Default")
      (node (ref "CORE-IO") (pin "17") (pinfunction "17_17") (pintype "passive"))
      (node (ref "IC26") (pin "6") (pinfunction "A5_6") (pintype "bidirectional"))
    )
    (net (code "92") (name "PIA-B5") (class "Default")
      (node (ref "CORE-IO") (pin "18") (pinfunction "18_18") (pintype "passive"))
      (node (ref "IC26") (pin "7") (pinfunction "A6_7") (pintype "bidirectional"))
    )
    (net (code "93") (name "PIA-B6") (class "Default")
      (node (ref "CORE-IO") (pin "19") (pinfunction "19_19") (pintype "passive"))
      (node (ref "IC26") (pin "8") (pinfunction "A7_8") (pintype "bidirectional"))
    )
    (net (code "94") (name "PIA-B7") (class "Default")
      (node (ref "CORE-IO") (pin "20") (pinfunction "20_20") (pintype "passive"))
      (node (ref "IC26") (pin "9") (pinfunction "A8_9") (pintype "bidirectional"))
    )
    (net (code "95") (name "Q") (class "Default")
      (node (ref "IC17") (pin "35") (pinfunction "Q_35") (pintype "input"))
      (node (ref "IC2") (pin "12") (pinfunction "Q_12") (pintype "output"))
      (node (ref "IC2") (pin "7") (pinfunction "J_7") (pintype "input"))
    )
    (net (code "96") (name "RX") (class "Default")
      (node (ref "IC20") (pin "12") (pinfunction "R1OUT_12") (pintype "output"))
      (node (ref "IC21") (pin "2") (pinfunction "RXDATA_2") (pintype "input"))
    )
    (net (code "97") (name "RXD") (class "Default")
      (node (ref "COM") (pin "3") (pinfunction "3_3") (pintype "passive"))
      (node (ref "IC20") (pin "13") (pinfunction "R1IN_13") (pintype "input"))
      (node (ref "RS-232") (pin "3") (pinfunction "3_3") (pintype "passive"))
    )
    (net (code "98") (name "R{slash}~{W}") (class "Default")
      (node (ref "EPROM") (pin "5") (pinfunction "5_5") (pintype "passive"))
      (node (ref "IC17") (pin "32") (pinfunction "R/~{W}_32") (pintype "output"))
      (node (ref "IC21") (pin "13") (pinfunction "R/~{W}_13") (pintype "input"))
      (node (ref "IC22") (pin "27") (pinfunction "~{WE}_27") (pintype "input"))
      (node (ref "IC24") (pin "21") (pinfunction "R/~{W}_21") (pintype "input"))
    )
    (net (code "99") (name "TX") (class "Default")
      (node (ref "IC20") (pin "11") (pinfunction "T1IN_11") (pintype "input"))
      (node (ref "IC21") (pin "6") (pinfunction "TXDATA_6") (pintype "output"))
    )
    (net (code "100") (name "TXD") (class "Default")
      (node (ref "COM") (pin "2") (pinfunction "2_2") (pintype "passive"))
      (node (ref "IC20") (pin "14") (pinfunction "T1OUT_14") (pintype "output"))
      (node (ref "RS-232") (pin "1") (pinfunction "1_1") (pintype "passive"))
    )
    (net (code "101") (name "VCC") (class "Default")
      (node (ref "BYP17") (pin "1") (pinfunction "1_1") (pintype "passive"))
      (node (ref "BYP18") (pin "1") (pinfunction "1_1") (pintype "passive"))
      (node (ref "BYP19") (pin "1") (pinfunction "1_1") (pintype "passive"))
      (node (ref "BYP2") (pin "1") (pinfunction "1_1") (pintype "passive"))
      (node (ref "BYP20") (pin "1") (pinfunction "1_1") (pintype "passive"))
      (node (ref "BYP21") (pin "1") (pinfunction "1_1") (pintype "passive"))
      (node (ref "BYP22") (pin "1") (pinfunction "1_1") (pintype "passive"))
      (node (ref "BYP23") (pin "1") (pinfunction "1_1") (pintype "passive"))
      (node (ref "BYP24") (pin "1") (pinfunction "1_1") (pintype "passive"))
      (node (ref "BYP25") (pin "1") (pinfunction "1_1") (pintype "passive"))
      (node (ref "BYP26") (pin "1") (pinfunction "1_1") (pintype "passive"))
      (node (ref "BYP27") (pin "1") (pinfunction "1_1") (pintype "passive"))
      (node (ref "BYP28") (pin "1") (pinfunction "1_1") (pintype "passive"))
      (node (ref "BYP29") (pin "1") (pinfunction "1_1") (pintype "passive"))
      (node (ref "C10") (pin "1") (pinfunction "1_1") (pintype "passive"))
      (node (ref "CORE-IO") (pin "12") (pinfunction "12_12") (pintype "passive"))
      (node (ref "CORE-IO") (pin "9") (pinfunction "9_9") (pintype "passive"))
      (node (ref "DEBUG") (pin "2") (pinfunction "2_2") (pintype "passive"))
      (node (ref "EP-1") (pin "3") (pinfunction "3_3") (pintype "passive"))
      (node (ref "EPROM") (pin "1") (pinfunction "1_1") (pintype "passive"))
      (node (ref "IC17") (pin "7") (pinfunction "VCC_7") (pintype "power_in"))
      (node (ref "IC2") (pin "2") (pinfunction "CL_2") (pintype "input"))
      (node (ref "IC2") (pin "6") (pinfunction "CL_6") (pintype "input"))
      (node (ref "IC21") (pin "10") (pinfunction "CS1_10") (pintype "input"))
      (node (ref "IC21") (pin "12") (pinfunction "VCC_12") (pintype "power_in"))
      (node (ref "IC21") (pin "8") (pinfunction "CS0_8") (pintype "input"))
      (node (ref "IC22") (pin "28") (pinfunction "VCC_28") (pintype "power_in"))
      (node (ref "IC23") (pin "1") (pinfunction "VPP_1") (pintype "input"))
      (node (ref "IC23") (pin "28") (pinfunction "VCC_28") (pintype "power_in"))
      (node (ref "IC24") (pin "20") (pinfunction "VCC_20") (pintype "power_in"))
      (node (ref "IC24") (pin "22") (pinfunction "CS0_22") (pintype "input"))
      (node (ref "IC24") (pin "24") (pinfunction "CS1_24") (pintype "input"))
      (node (ref "IC27") (pin "10") (pinfunction "R_10") (pintype "input"))
      (node (ref "IC27") (pin "14") (pinfunction "V+_14") (pintype "power_in"))
      (node (ref "IC27") (pin "4") (pinfunction "R_4") (pintype "input"))
      (node (ref "JP4") (pin "2") (pinfunction "2_2") (pintype "passive"))
      (node (ref "QG1") (pin "14") (pinfunction "VCC_14") (pintype "power_in"))
      (node (ref "R1") (pin "2") (pinfunction "2_2") (pintype "passive"))
      (node (ref "R12") (pin "2") (pinfunction "2_2") (pintype "passive"))
      (node (ref "R14") (pin "2") (pinfunction "2_2") (pintype "passive"))
      (node (ref "R2") (pin "2") (pinfunction "2_2") (pintype "passive"))
      (node (ref "R3") (pin "2") (pinfunction "2_2") (pintype "passive"))
      (node (ref "R5") (pin "2") (pinfunction "2_2") (pintype "passive"))
      (node (ref "R6") (pin "2") (pinfunction "2_2") (pintype "passive"))
      (node (ref "R7") (pin "2") (pinfunction "2_2") (pintype "passive"))
      (node (ref "R8") (pin "2") (pinfunction "2_2") (pintype "passive"))
      (node (ref "R9") (pin "2") (pinfunction "2_2") (pintype "passive"))
    )
    (net (code "102") (name "unconnected-(COM-Pad1)") (class "Default")
      (node (ref "COM") (pin "1") (pinfunction "1_1") (pintype "passive"))
    )
    (net (code "103") (name "unconnected-(COM-Pad9)") (class "Default")
      (node (ref "COM") (pin "9") (pinfunction "9_9") (pintype "passive"))
    )
    (net (code "104") (name "unconnected-(IC17A-AVMA-Pad36)") (class "Default")
      (node (ref "IC17") (pin "36") (pinfunction "AVMA_36") (pintype "output"))
    )
    (net (code "105") (name "unconnected-(IC17A-BA-Pad6)") (class "Default")
      (node (ref "IC17") (pin "6") (pinfunction "BA_6") (pintype "output"))
    )
    (net (code "106") (name "unconnected-(IC17A-BS-Pad5)") (class "Default")
      (node (ref "IC17") (pin "5") (pinfunction "BS_5") (pintype "output"))
    )
    (net (code "107") (name "unconnected-(IC17A-BUSY-Pad33)") (class "Default")
      (node (ref "IC17") (pin "33") (pinfunction "BUSY_33") (pintype "output"))
    )
    (net (code "108") (name "unconnected-(IC17A-LIC-Pad38)") (class "Default")
      (node (ref "IC17") (pin "38") (pinfunction "LIC_38") (pintype "output"))
    )
    (net (code "109") (name "unconnected-(IC19A-Y0-Pad15)") (class "Default")
      (node (ref "IC19") (pin "15") (pinfunction "Y0_15") (pintype "output"))
    )
    (net (code "110") (name "unconnected-(IC19A-Y1-Pad14)") (class "Default")
      (node (ref "IC19") (pin "14") (pinfunction "Y1_14") (pintype "output"))
    )
    (net (code "111") (name "unconnected-(IC19A-Y2-Pad13)") (class "Default")
      (node (ref "IC19") (pin "13") (pinfunction "Y2_13") (pintype "output"))
    )
    (net (code "112") (name "unconnected-(IC19A-Y3-Pad12)") (class "Default")
      (node (ref "IC19") (pin "12") (pinfunction "Y3_12") (pintype "output"))
    )
    (net (code "113") (name "unconnected-(IC19A-Y4-Pad11)") (class "Default")
      (node (ref "IC19") (pin "11") (pinfunction "Y4_11") (pintype "output"))
    )
    (net (code "114") (name "unconnected-(IC19A-Y5-Pad10)") (class "Default")
      (node (ref "IC19") (pin "10") (pinfunction "Y5_10") (pintype "output"))
    )
    (net (code "115") (name "unconnected-(IC20A-R2OUT-Pad9)") (class "Default")
      (node (ref "IC20") (pin "9") (pinfunction "R2OUT_9") (pintype "output"))
    )
    (net (code "116") (name "unconnected-(IC22-NC-Pad1)") (class "Default")
      (node (ref "IC22") (pin "1") (pinfunction "NC_1") (pintype "no_connect"))
    )
    (net (code "117") (name "unconnected-(IC28A-Y1-Pad5)") (class "Default")
      (node (ref "IC28") (pin "5") (pinfunction "Y1_5") (pintype "output"))
    )
    (net (code "118") (name "unconnected-(IC28A-Y2-Pad6)") (class "Default")
      (node (ref "IC28") (pin "6") (pinfunction "Y2_6") (pintype "output"))
    )
    (net (code "119") (name "unconnected-(IC28B-Y0-Pad12)") (class "Default")
      (node (ref "IC28") (pin "12") (pinfunction "Y0_12") (pintype "output"))
    )
    (net (code "120") (name "~{4-B}") (class "Default")
      (node (ref "IC28") (pin "9") (pinfunction "Y3_9") (pintype "output"))
      (node (ref "IC29") (pin "20") (pinfunction "~{CE}_20") (pintype "input"))
      (node (ref "IC29") (pin "22") (pinfunction "~{OE}_22") (pintype "input"))
    )
    (net (code "121") (name "~{0123}") (class "Default")
      (node (ref "IC19") (pin "5") (pinfunction "G2B_5") (pintype "input"))
      (node (ref "IC22") (pin "20") (pinfunction "~{CS1}_20") (pintype "input"))
      (node (ref "IC22") (pin "22") (pinfunction "~{OE}_22") (pintype "input"))
      (node (ref "IC28") (pin "11") (pinfunction "Y1_11") (pintype "output"))
    )
    (net (code "122") (name "~{CDEF}") (class "Default")
      (node (ref "IC23") (pin "20") (pinfunction "~{CE}_20") (pintype "input"))
      (node (ref "IC23") (pin "22") (pinfunction "~{OE}_22") (pintype "input"))
      (node (ref "IC28") (pin "10") (pinfunction "Y2_10") (pintype "output"))
    )
    (net (code "123") (name "~{EP1}") (class "Default")
      (node (ref "IC28") (pin "14") (pinfunction "A_14") (pintype "input"))
      (node (ref "IC28") (pin "7") (pinfunction "Y3_7") (pintype "output"))
    )
    (net (code "124") (name "~{FIRQ}") (class "Default")
      (node (ref "IC17") (pin "4") (pinfunction "FIRQ_4") (pintype "input"))
      (node (ref "IC24") (pin "37") (pinfunction "IRQB_37") (pintype "open_collector"))
      (node (ref "IC24") (pin "38") (pinfunction "IRQA_38") (pintype "open_collector"))
      (node (ref "R8") (pin "1") (pinfunction "1_1") (pintype "passive"))
    )
    (net (code "125") (name "~{HLT}") (class "Default")
      (node (ref "IC17") (pin "40") (pinfunction "HALT_40") (pintype "input"))
      (node (ref "R5") (pin "1") (pinfunction "1_1") (pintype "passive"))
    )
    (net (code "126") (name "~{IO-E}") (class "Default")
      (node (ref "IC19") (pin "9") (pinfunction "Y6_9") (pintype "output"))
      (node (ref "IC24") (pin "23") (pinfunction "CS2_23") (pintype "input"))
    )
    (net (code "127") (name "~{IO-F}") (class "Default")
      (node (ref "IC19") (pin "7") (pinfunction "Y7_7") (pintype "output"))
      (node (ref "IC21") (pin "9") (pinfunction "CS2_9") (pintype "input"))
    )
    (net (code "128") (name "~{IRQ}") (class "Default")
      (node (ref "IC17") (pin "3") (pinfunction "IRQ_3") (pintype "input"))
      (node (ref "IC21") (pin "7") (pinfunction "IRQ_7") (pintype "output"))
      (node (ref "R7") (pin "1") (pinfunction "1_1") (pintype "passive"))
    )
    (net (code "129") (name "~{NMI}") (class "Default")
      (node (ref "IC17") (pin "2") (pinfunction "NMI_2") (pintype "input"))
      (node (ref "R6") (pin "1") (pinfunction "1_1") (pintype "passive"))
    )
    (net (code "130") (name "~{RST}") (class "Default")
      (node (ref "IC17") (pin "37") (pinfunction "RESET_37") (pintype "input"))
      (node (ref "IC18") (pin "6") (pinfunction "O_6") (pintype "output"))
      (node (ref "IC24") (pin "34") (pinfunction "RESET_34") (pintype "input"))
    )
  )
)
